# regulator.net
KiCad netlist of a schematic drawn in EAGLE
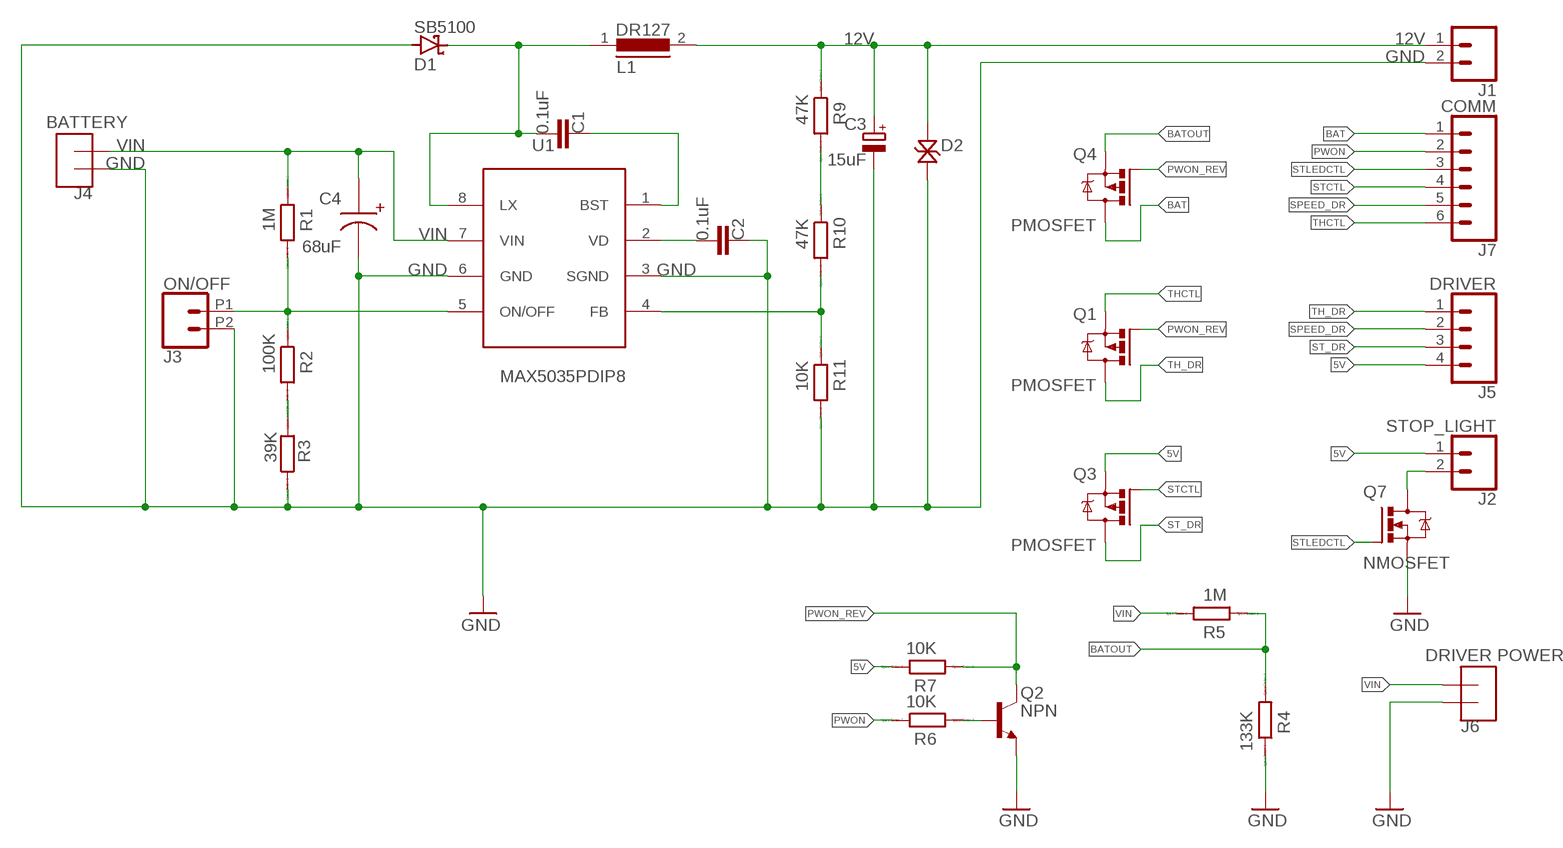
[diagram p0: schematic, sheet 1]

(export (version "E")
  (design (tool "Eeschema 10.0.6"))
  (components
    (comp (ref "C1")
      (value "0.1uF")
      (footprint "eagle-import:CAPC3216X135")
      (libsource (lib "eagle-import") (part "CCHIP-1206(3216-METRIC)_"))
    )
    (comp (ref "C2")
      (value "0.1uF")
      (footprint "eagle-import:CAPC3216X135")
      (libsource (lib "eagle-import") (part "CCHIP-1206(3216-METRIC)_"))
    )
    (comp (ref "C3")
      (value "15uF")
      (footprint "eagle-import:CAPMP7343X310N")
      (libsource (lib "eagle-import") (part "C-POLTANTALUM-2917(7343-METRIC)_"))
    )
    (comp (ref "C4")
      (value "68uF")
      (footprint "eagle-import:CAPAE1230X1250N")
      (libsource (lib "eagle-import") (part "CPANASONIC_H13"))
    )
    (comp (ref "D1")
      (value "SB5100")
      (footprint "eagle-import:DO201AD")
      (fields
        (field (name "DIGIKEY_PART_NUMBER") "MBR360GOS-ND")
        (field (name "MANUFACTURER") "ON Semiconductor")
        (field (name "MPN") "MBR360G")
        (field (name "CREATED_BY") "PCBLayout.com")
      )
      (libsource (lib "eagle-import") (part "MBR360G"))
    )
    (comp (ref "D2")
      (value "P4SMAJ12CA")
      (footprint "eagle-import:DIOM5027X220N")
      (libsource (lib "eagle-import") (part "TVS_DIODESMA"))
    )
    (comp (ref "J1")
      (value "CONN_02PTH3")
      (footprint "eagle-import:1X02_LONGPADS")
      (libsource (lib "eagle-import") (part "CONN_02PTH3"))
    )
    (comp (ref "J2")
      (value "STOP_LIGHT")
      (footprint "eagle-import:1X02")
      (libsource (lib "eagle-import") (part "CONN_02"))
    )
    (comp (ref "J3")
      (value "ON/OFF")
      (footprint "eagle-import:1X02_2.54_SCREWTERM")
      (libsource (lib "eagle-import") (part "CONN_022.54MM_SCREWTERM"))
    )
    (comp (ref "J4")
      (value "BATTERY")
      (footprint "eagle-import:XT60")
      (libsource (lib "eagle-import") (part "XT60"))
    )
    (comp (ref "J5")
      (value "DRIVER")
      (footprint "eagle-import:1X04")
      (libsource (lib "eagle-import") (part "CONN_04"))
    )
    (comp (ref "J6")
      (value "DRIVER POWER")
      (footprint "eagle-import:XT60")
      (libsource (lib "eagle-import") (part "XT60"))
    )
    (comp (ref "J7")
      (value "COMM")
      (footprint "eagle-import:1X06_LONGPADS")
      (libsource (lib "eagle-import") (part "CONN_06LONGPADS"))
    )
    (comp (ref "L1")
      (value "DR127")
      (footprint "eagle-import:DR127")
      (libsource (lib "eagle-import") (part "DR127"))
    )
    (comp (ref "Q1")
      (value "PMOSFET")
      (footprint "eagle-import:SOT23")
      (libsource (lib "eagle-import") (part "PMOSFETSOT23_"))
    )
    (comp (ref "Q2")
      (value "NPN")
      (footprint "eagle-import:SOT95P237X112-3N")
      (libsource (lib "eagle-import") (part "NPNSOT23_"))
    )
    (comp (ref "Q3")
      (value "PMOSFET")
      (footprint "eagle-import:SOT23")
      (libsource (lib "eagle-import") (part "PMOSFETSOT23_"))
    )
    (comp (ref "Q4")
      (value "PMOSFET")
      (footprint "eagle-import:SOT23")
      (libsource (lib "eagle-import") (part "PMOSFETSOT23_"))
    )
    (comp (ref "Q7")
      (value "NMOSFET")
      (footprint "eagle-import:SOT23")
      (libsource (lib "eagle-import") (part "NMOSFETSOT23"))
    )
    (comp (ref "R1")
      (value "1M")
      (footprint "eagle-import:R1206")
      (libsource (lib "eagle-import") (part "RR1206"))
    )
    (comp (ref "R2")
      (value "100K")
      (footprint "eagle-import:R1206")
      (libsource (lib "eagle-import") (part "RR1206"))
    )
    (comp (ref "R3")
      (value "39K")
      (footprint "eagle-import:R1206")
      (libsource (lib "eagle-import") (part "RR1206"))
    )
    (comp (ref "R4")
      (value "133K")
      (footprint "eagle-import:R1206")
      (libsource (lib "eagle-import") (part "RR1206"))
    )
    (comp (ref "R5")
      (value "1M")
      (footprint "eagle-import:R1206")
      (libsource (lib "eagle-import") (part "RR1206"))
    )
    (comp (ref "R6")
      (value "10K")
      (footprint "eagle-import:R1206")
      (libsource (lib "eagle-import") (part "RR1206"))
    )
    (comp (ref "R7")
      (value "10K")
      (footprint "eagle-import:R1206")
      (libsource (lib "eagle-import") (part "RR1206"))
    )
    (comp (ref "R9")
      (value "47K")
      (footprint "eagle-import:R1206")
      (libsource (lib "eagle-import") (part "RR1206"))
    )
    (comp (ref "R10")
      (value "47K")
      (footprint "eagle-import:R1206")
      (libsource (lib "eagle-import") (part "RR1206"))
    )
    (comp (ref "R11")
      (value "10K")
      (footprint "eagle-import:R1206")
      (libsource (lib "eagle-import") (part "RR1206"))
    )
    (comp (ref "U1")
      (value "MAX5035PDIP8")
      (footprint "eagle-import:DIP826W56P254L937H458Q8B")
      (libsource (lib "eagle-import") (part "MAX5035PDIP8"))
    )
  )
  (nets
    (net (code "1") (name "/12V") (class "Default")
      (node (ref "C3") (pin "1") (pinfunction "+_1") (pintype "passive"))
      (node (ref "D2") (pin "1") (pinfunction "P$1_1") (pintype "bidirectional"))
      (node (ref "J1") (pin "1") (pinfunction "1_1") (pintype "passive"))
      (node (ref "L1") (pin "2") (pinfunction "2_2") (pintype "passive"))
      (node (ref "R9") (pin "1") (pinfunction "1_1") (pintype "passive"))
    )
    (net (code "2") (name "5V") (class "Default")
      (node (ref "J2") (pin "1") (pinfunction "1_1") (pintype "passive"))
      (node (ref "J5") (pin "4") (pinfunction "4_4") (pintype "passive"))
      (node (ref "Q3") (pin "2") (pinfunction "S_2") (pintype "passive"))
      (node (ref "R7") (pin "1") (pinfunction "1_1") (pintype "passive"))
    )
    (net (code "3") (name "BAT") (class "Default")
      (node (ref "J7") (pin "1") (pinfunction "1_1") (pintype "passive"))
      (node (ref "Q4") (pin "3") (pinfunction "D_3") (pintype "passive"))
    )
    (net (code "4") (name "BATOUT") (class "Default")
      (node (ref "Q4") (pin "2") (pinfunction "S_2") (pintype "passive"))
      (node (ref "R4") (pin "2") (pinfunction "2_2") (pintype "passive"))
      (node (ref "R5") (pin "1") (pinfunction "1_1") (pintype "passive"))
    )
    (net (code "5") (name "GND") (class "Default")
      (node (ref "C2") (pin "1") (pinfunction "1_1") (pintype "passive"))
      (node (ref "C3") (pin "2") (pinfunction "-_2") (pintype "passive"))
      (node (ref "C4") (pin "2") (pinfunction "P$2_2") (pintype "power_in"))
      (node (ref "D1") (pin "A") (pinfunction "A_A") (pintype "passive"))
      (node (ref "D2") (pin "2") (pinfunction "P$2_2") (pintype "bidirectional"))
      (node (ref "J1") (pin "2") (pinfunction "2_2") (pintype "passive"))
      (node (ref "J3") (pin "P2") (pinfunction "2_P2") (pintype "passive"))
      (node (ref "J4") (pin "GND") (pinfunction "P$1_GND") (pintype "power_in"))
      (node (ref "J6") (pin "GND") (pinfunction "P$1_GND") (pintype "power_in"))
      (node (ref "Q2") (pin "1") (pinfunction "E_1") (pintype "passive"))
      (node (ref "Q7") (pin "2") (pinfunction "S_2") (pintype "passive"))
      (node (ref "R11") (pin "2") (pinfunction "2_2") (pintype "passive"))
      (node (ref "R3") (pin "1") (pinfunction "1_1") (pintype "passive"))
      (node (ref "R4") (pin "1") (pinfunction "1_1") (pintype "passive"))
      (node (ref "U1") (pin "3") (pinfunction "SGND_3") (pintype "input"))
      (node (ref "U1") (pin "6") (pinfunction "GND_6") (pintype "power_in"))
    )
    (net (code "6") (name "Net-(J3-1)") (class "Default")
      (node (ref "J3") (pin "P1") (pinfunction "1_P1") (pintype "passive"))
      (node (ref "R1") (pin "2") (pinfunction "2_2") (pintype "passive"))
      (node (ref "R2") (pin "1") (pinfunction "1_1") (pintype "passive"))
      (node (ref "U1") (pin "5") (pinfunction "ON/OFF_5") (pintype "input"))
    )
    (net (code "7") (name "Net-(Q2-B)") (class "Default")
      (node (ref "Q2") (pin "2") (pinfunction "B_2") (pintype "passive"))
      (node (ref "R6") (pin "2") (pinfunction "2_2") (pintype "passive"))
    )
    (net (code "8") (name "Net-(Q7-D)") (class "Default")
      (node (ref "J2") (pin "2") (pinfunction "2_2") (pintype "passive"))
      (node (ref "Q7") (pin "3") (pinfunction "D_3") (pintype "passive"))
    )
    (net (code "9") (name "Net-(R2-Pad2)") (class "Default")
      (node (ref "R2") (pin "2") (pinfunction "2_2") (pintype "passive"))
      (node (ref "R3") (pin "2") (pinfunction "2_2") (pintype "passive"))
    )
    (net (code "10") (name "Net-(R10-Pad1)") (class "Default")
      (node (ref "R10") (pin "1") (pinfunction "1_1") (pintype "passive"))
      (node (ref "R9") (pin "2") (pinfunction "2_2") (pintype "passive"))
    )
    (net (code "11") (name "Net-(U1-BST)") (class "Default")
      (node (ref "C1") (pin "1") (pinfunction "1_1") (pintype "passive"))
      (node (ref "U1") (pin "1") (pinfunction "BST_1") (pintype "input"))
    )
    (net (code "12") (name "Net-(U1-FB)") (class "Default")
      (node (ref "R10") (pin "2") (pinfunction "2_2") (pintype "passive"))
      (node (ref "R11") (pin "1") (pinfunction "1_1") (pintype "passive"))
      (node (ref "U1") (pin "4") (pinfunction "FB_4") (pintype "input"))
    )
    (net (code "13") (name "Net-(U1-LX)") (class "Default")
      (node (ref "C1") (pin "2") (pinfunction "2_2") (pintype "passive"))
      (node (ref "D1") (pin "C") (pinfunction "C_C") (pintype "passive"))
      (node (ref "L1") (pin "1") (pinfunction "1_1") (pintype "passive"))
      (node (ref "U1") (pin "8") (pinfunction "LX_8") (pintype "power_in"))
    )
    (net (code "14") (name "Net-(U1-VD)") (class "Default")
      (node (ref "C2") (pin "2") (pinfunction "2_2") (pintype "passive"))
      (node (ref "U1") (pin "2") (pinfunction "VD_2") (pintype "input"))
    )
    (net (code "15") (name "PWON") (class "Default")
      (node (ref "J7") (pin "2") (pinfunction "2_2") (pintype "passive"))
      (node (ref "R6") (pin "1") (pinfunction "1_1") (pintype "passive"))
    )
    (net (code "16") (name "PWON_REV") (class "Default")
      (node (ref "Q1") (pin "1") (pinfunction "G_1") (pintype "passive"))
      (node (ref "Q2") (pin "3") (pinfunction "C_3") (pintype "passive"))
      (node (ref "Q4") (pin "1") (pinfunction "G_1") (pintype "passive"))
      (node (ref "R7") (pin "2") (pinfunction "2_2") (pintype "passive"))
    )
    (net (code "17") (name "SPEED_DR") (class "Default")
      (node (ref "J5") (pin "2") (pinfunction "2_2") (pintype "passive"))
      (node (ref "J7") (pin "5") (pinfunction "5_5") (pintype "passive"))
    )
    (net (code "18") (name "STCTL") (class "Default")
      (node (ref "J7") (pin "4") (pinfunction "4_4") (pintype "passive"))
      (node (ref "Q3") (pin "1") (pinfunction "G_1") (pintype "passive"))
    )
    (net (code "19") (name "STLEDCTL") (class "Default")
      (node (ref "J7") (pin "3") (pinfunction "3_3") (pintype "passive"))
      (node (ref "Q7") (pin "1") (pinfunction "G_1") (pintype "passive"))
    )
    (net (code "20") (name "ST_DR") (class "Default")
      (node (ref "J5") (pin "3") (pinfunction "3_3") (pintype "passive"))
      (node (ref "Q3") (pin "3") (pinfunction "D_3") (pintype "passive"))
    )
    (net (code "21") (name "THCTL") (class "Default")
      (node (ref "J7") (pin "6") (pinfunction "6_6") (pintype "passive"))
      (node (ref "Q1") (pin "2") (pinfunction "S_2") (pintype "passive"))
    )
    (net (code "22") (name "TH_DR") (class "Default")
      (node (ref "J5") (pin "1") (pinfunction "1_1") (pintype "passive"))
      (node (ref "Q1") (pin "3") (pinfunction "D_3") (pintype "passive"))
    )
    (net (code "23") (name "VIN") (class "Default")
      (node (ref "C4") (pin "1") (pinfunction "P$1_1") (pintype "power_in"))
      (node (ref "J4") (pin "VCC") (pinfunction "P$2_VCC") (pintype "power_in"))
      (node (ref "J6") (pin "VCC") (pinfunction "P$2_VCC") (pintype "power_in"))
      (node (ref "R1") (pin "1") (pinfunction "1_1") (pintype "passive"))
      (node (ref "R5") (pin "2") (pinfunction "2_2") (pintype "passive"))
      (node (ref "U1") (pin "7") (pinfunction "VIN_7") (pintype "power_in"))
    )
  )
)
